# EquaBoardDB.net
KiCad netlist of a schematic drawn in EAGLE
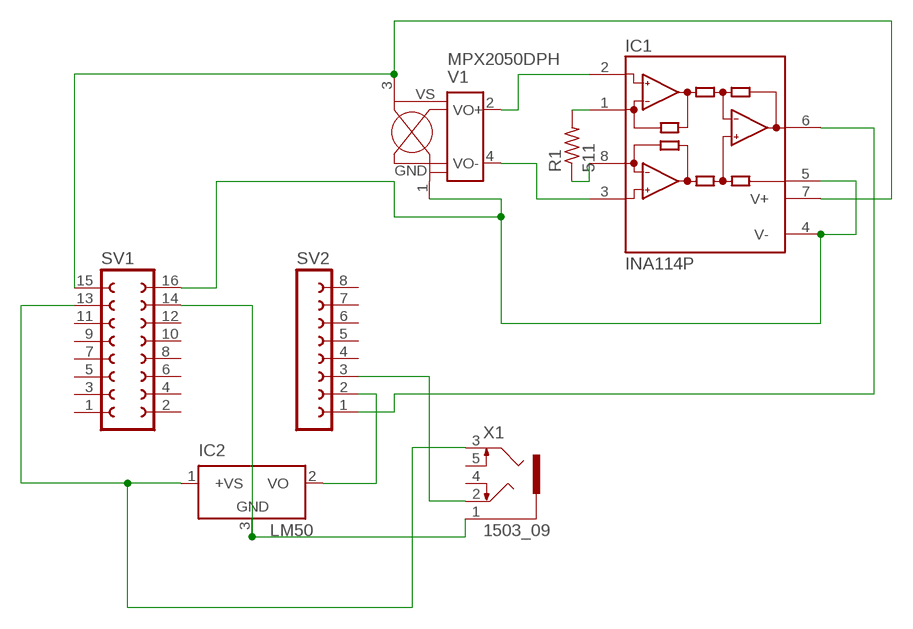
[diagram p0: schematic, sheet 1]

(export (version "E")
  (design (tool "Eeschema 10.0.6"))
  (components
    (comp (ref "IC1")
      (value "INA114P")
      (footprint "eagle-import:DIL08")
      (fields (field (name "MF") "TEXAS INSTRUMENTS") (field (name "MPN") "INA114BP"))
      (libsource (lib "eagle-import") (part "INA114P"))
    )
    (comp (ref "IC2")
      (value "LM50")
      (footprint "eagle-import:SOT23")
      (libsource (lib "eagle-import") (part "LM50"))
    )
    (comp (ref "R1")
      (value "511")
      (footprint "eagle-import:0204_7")
      (libsource (lib "eagle-import") (part "R-US_0204/7"))
    )
    (comp (ref "SV1")
      (value "FE08-2")
      (footprint "eagle-import:FE08-2")
      (libsource (lib "eagle-import") (part "FE08-2"))
    )
    (comp (ref "SV2")
      (value "FE08-1")
      (footprint "eagle-import:FE08")
      (libsource (lib "eagle-import") (part "FE08-1"))
    )
    (comp (ref "V1")
      (value "MPX2050DPH")
      (footprint "eagle-import:MPX2050DPH")
      (libsource (lib "eagle-import") (part "MPX2050DPH"))
    )
    (comp (ref "X1")
      (value "1503_09")
      (footprint "eagle-import:1503_09")
      (libsource (lib "eagle-import") (part "1503_09"))
    )
  )
  (nets
    (net (code "1") (name "Net-(IC1-+IN)") (class "Default")
      (node (ref "IC1") (pin "3") (pinfunction "+IN_3") (pintype "input"))
      (node (ref "V1") (pin "4") (pinfunction "VO-_4") (pintype "passive"))
    )
    (net (code "2") (name "Net-(IC1--IN)") (class "Default")
      (node (ref "IC1") (pin "2") (pinfunction "-IN_2") (pintype "input"))
      (node (ref "V1") (pin "2") (pinfunction "VO+_2") (pintype "passive"))
    )
    (net (code "3") (name "Net-(IC1-OUT)") (class "Default")
      (node (ref "IC1") (pin "6") (pinfunction "OUT_6") (pintype "output"))
      (node (ref "SV2") (pin "1") (pinfunction "1_1") (pintype "passive"))
    )
    (net (code "4") (name "Net-(IC1-REF)") (class "Default")
      (node (ref "IC1") (pin "4") (pinfunction "V-_4") (pintype "power_in"))
      (node (ref "IC1") (pin "5") (pinfunction "REF_5") (pintype "passive"))
      (node (ref "SV1") (pin "16") (pinfunction "16_16") (pintype "passive"))
      (node (ref "V1") (pin "1") (pinfunction "GND_1") (pintype "passive"))
    )
    (net (code "5") (name "Net-(IC1-RG-Pad1)") (class "Default")
      (node (ref "IC1") (pin "1") (pinfunction "RG_1") (pintype "passive"))
      (node (ref "R1") (pin "2") (pinfunction "2_2") (pintype "passive"))
    )
    (net (code "6") (name "Net-(IC1-RG-Pad8)") (class "Default")
      (node (ref "IC1") (pin "8") (pinfunction "RG_8") (pintype "passive"))
      (node (ref "R1") (pin "1") (pinfunction "1_1") (pintype "passive"))
    )
    (net (code "7") (name "Net-(IC1-V+)") (class "Default")
      (node (ref "IC1") (pin "7") (pinfunction "V+_7") (pintype "power_in"))
      (node (ref "SV1") (pin "15") (pinfunction "15_15") (pintype "passive"))
      (node (ref "V1") (pin "3") (pinfunction "VS_3") (pintype "passive"))
    )
    (net (code "8") (name "Net-(IC2-+VS)") (class "Default")
      (node (ref "IC2") (pin "1") (pinfunction "+VS_1") (pintype "input"))
      (node (ref "SV1") (pin "13") (pinfunction "13_13") (pintype "passive"))
      (node (ref "X1") (pin "3") (pinfunction "3_3") (pintype "passive"))
    )
    (net (code "9") (name "Net-(IC2-GND)") (class "Default")
      (node (ref "IC2") (pin "3") (pinfunction "GND_3") (pintype "power_in"))
      (node (ref "SV1") (pin "14") (pinfunction "14_14") (pintype "passive"))
      (node (ref "X1") (pin "1") (pinfunction "1_1") (pintype "passive"))
    )
    (net (code "10") (name "Net-(IC2-VO)") (class "Default")
      (node (ref "IC2") (pin "2") (pinfunction "VO_2") (pintype "input"))
      (node (ref "SV2") (pin "2") (pinfunction "2_2") (pintype "passive"))
    )
    (net (code "11") (name "Net-(SV2-Pad3)") (class "Default")
      (node (ref "SV2") (pin "3") (pinfunction "3_3") (pintype "passive"))
      (node (ref "X1") (pin "2") (pinfunction "2_2") (pintype "passive"))
    )
    (net (code "12") (name "unconnected-(SV1-Pad1)") (class "Default")
      (node (ref "SV1") (pin "1") (pinfunction "1_1") (pintype "passive"))
    )
    (net (code "13") (name "unconnected-(SV1-Pad2)") (class "Default")
      (node (ref "SV1") (pin "2") (pinfunction "2_2") (pintype "passive"))
    )
    (net (code "14") (name "unconnected-(SV1-Pad3)") (class "Default")
      (node (ref "SV1") (pin "3") (pinfunction "3_3") (pintype "passive"))
    )
    (net (code "15") (name "unconnected-(SV1-Pad4)") (class "Default")
      (node (ref "SV1") (pin "4") (pinfunction "4_4") (pintype "passive"))
    )
    (net (code "16") (name "unconnected-(SV1-Pad5)") (class "Default")
      (node (ref "SV1") (pin "5") (pinfunction "5_5") (pintype "passive"))
    )
    (net (code "17") (name "unconnected-(SV1-Pad6)") (class "Default")
      (node (ref "SV1") (pin "6") (pinfunction "6_6") (pintype "passive"))
    )
    (net (code "18") (name "unconnected-(SV1-Pad7)") (class "Default")
      (node (ref "SV1") (pin "7") (pinfunction "7_7") (pintype "passive"))
    )
    (net (code "19") (name "unconnected-(SV1-Pad8)") (class "Default")
      (node (ref "SV1") (pin "8") (pinfunction "8_8") (pintype "passive"))
    )
    (net (code "20") (name "unconnected-(SV1-Pad9)") (class "Default")
      (node (ref "SV1") (pin "9") (pinfunction "9_9") (pintype "passive"))
    )
    (net (code "21") (name "unconnected-(SV1-Pad10)") (class "Default")
      (node (ref "SV1") (pin "10") (pinfunction "10_10") (pintype "passive"))
    )
    (net (code "22") (name "unconnected-(SV1-Pad11)") (class "Default")
      (node (ref "SV1") (pin "11") (pinfunction "11_11") (pintype "passive"))
    )
    (net (code "23") (name "unconnected-(SV1-Pad12)") (class "Default")
      (node (ref "SV1") (pin "12") (pinfunction "12_12") (pintype "passive"))
    )
    (net (code "24") (name "unconnected-(SV2-Pad4)") (class "Default")
      (node (ref "SV2") (pin "4") (pinfunction "4_4") (pintype "passive"))
    )
    (net (code "25") (name "unconnected-(SV2-Pad5)") (class "Default")
      (node (ref "SV2") (pin "5") (pinfunction "5_5") (pintype "passive"))
    )
    (net (code "26") (name "unconnected-(SV2-Pad6)") (class "Default")
      (node (ref "SV2") (pin "6") (pinfunction "6_6") (pintype "passive"))
    )
    (net (code "27") (name "unconnected-(SV2-Pad7)") (class "Default")
      (node (ref "SV2") (pin "7") (pinfunction "7_7") (pintype "passive"))
    )
    (net (code "28") (name "unconnected-(SV2-Pad8)") (class "Default")
      (node (ref "SV2") (pin "8") (pinfunction "8_8") (pintype "passive"))
    )
    (net (code "29") (name "unconnected-(X1-Pad4)") (class "Default")
      (node (ref "X1") (pin "4") (pinfunction "4_4") (pintype "passive"))
    )
    (net (code "30") (name "unconnected-(X1-Pad5)") (class "Default")
      (node (ref "X1") (pin "5") (pinfunction "5_5") (pintype "passive"))
    )
  )
)
